# Sheet1.net
KiCad netlist of a schematic drawn in Altium Designer
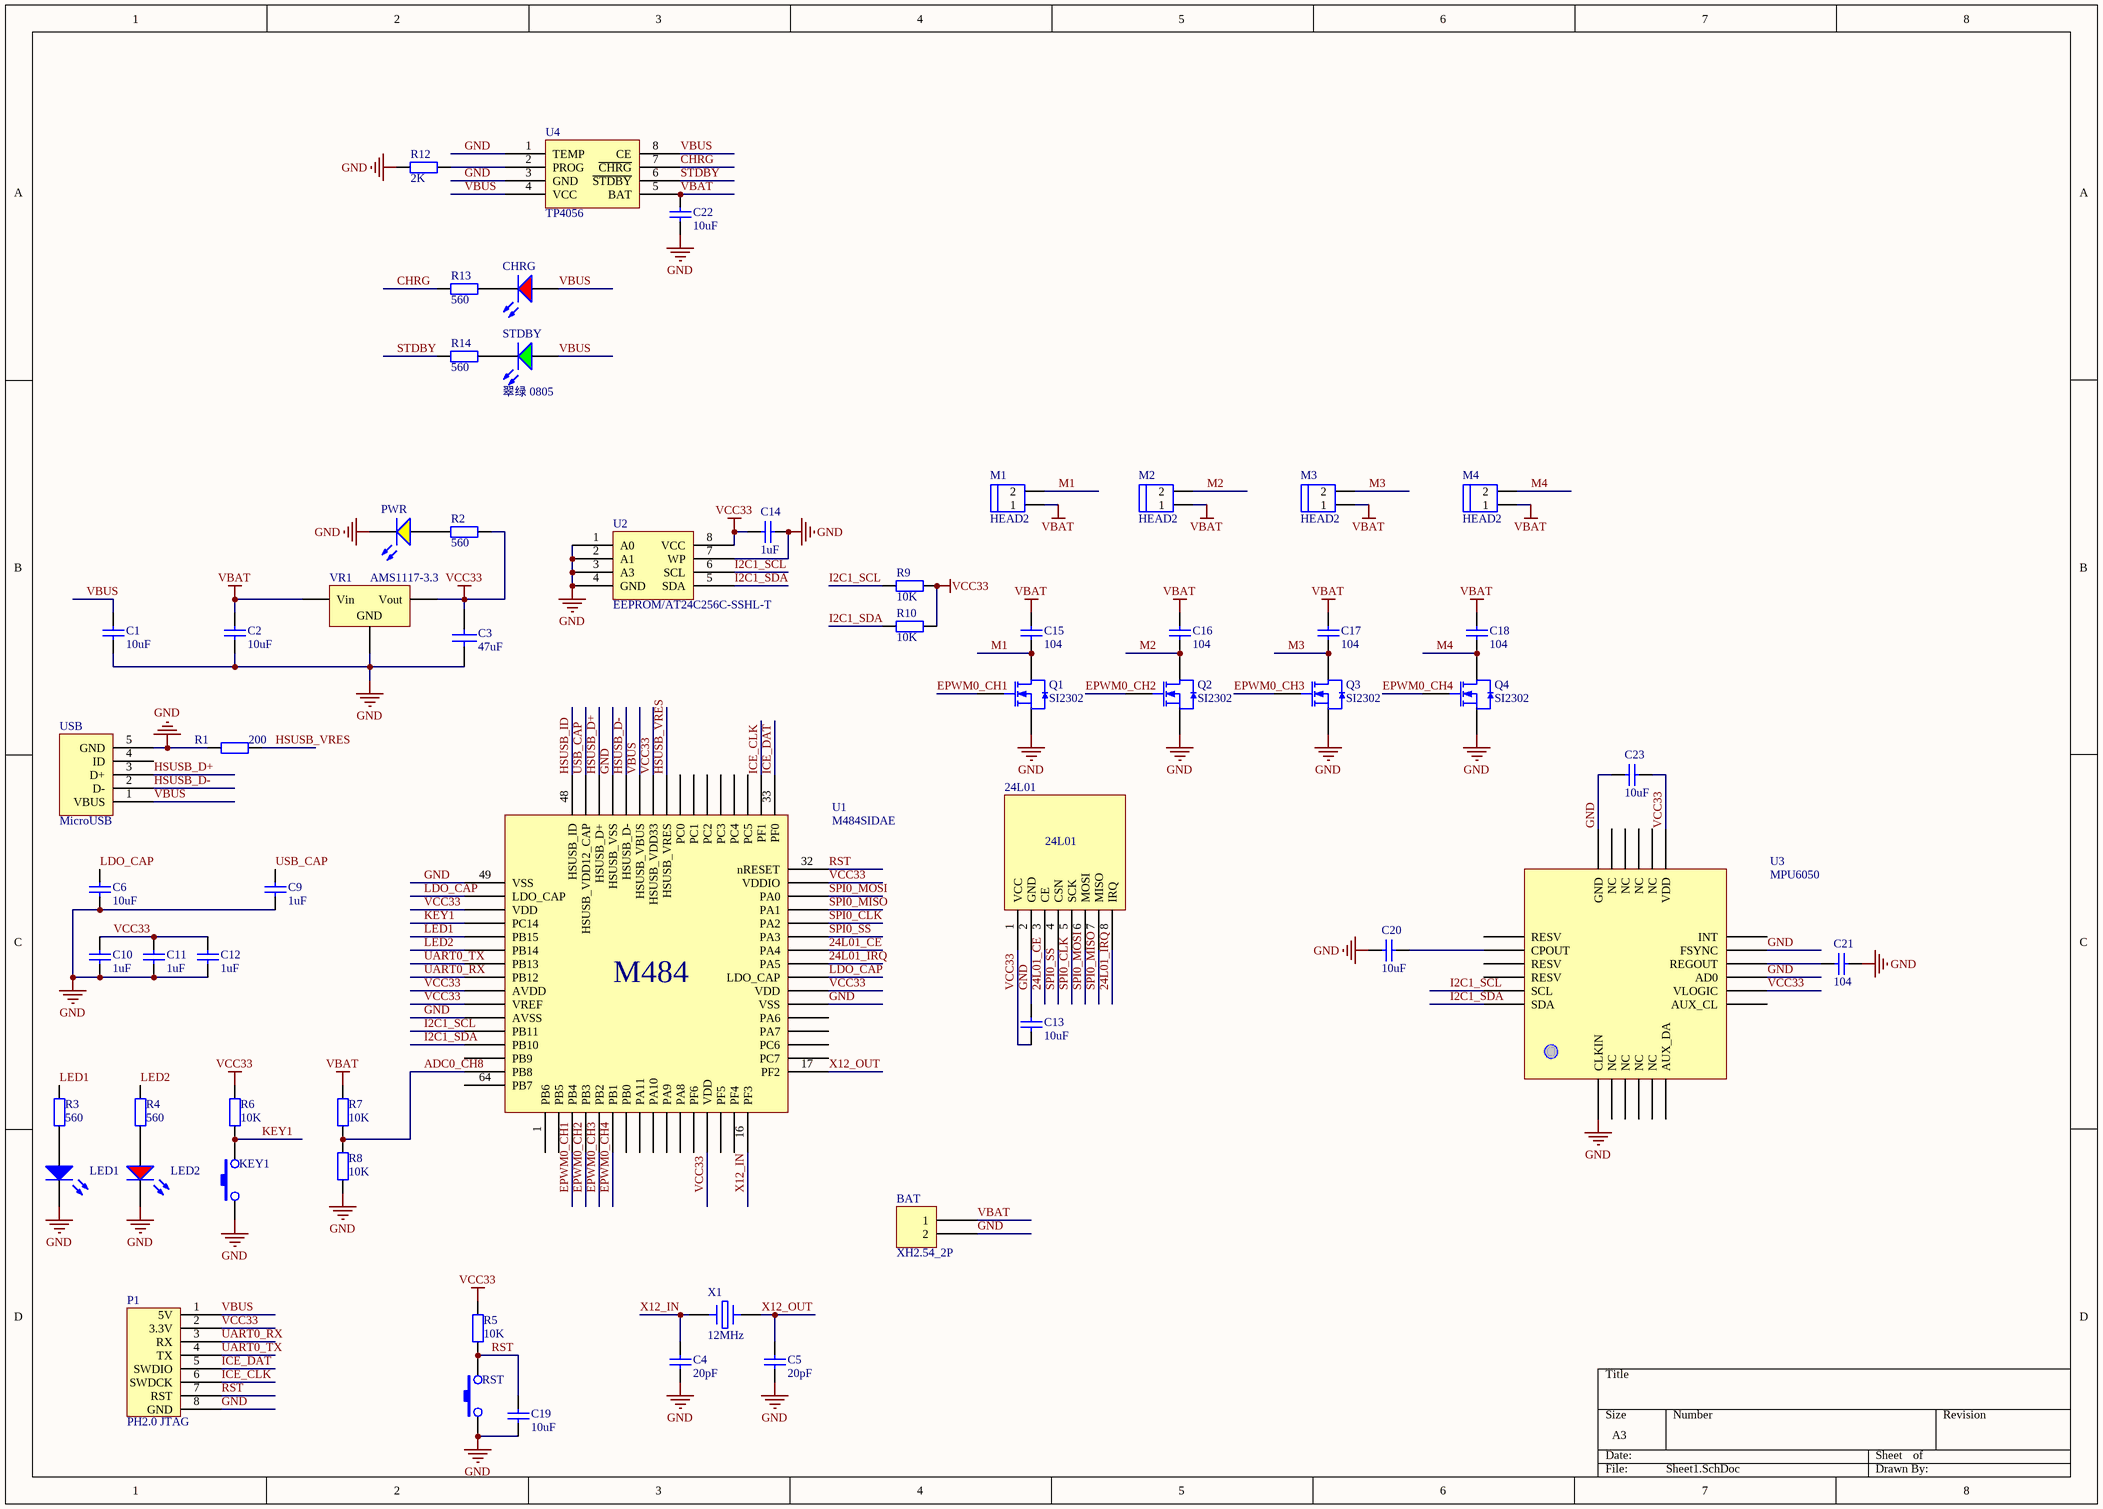
[diagram p0: Sheet1.SchDoc]

(export (version "E")
  (design (tool "Eeschema 10.0.6"))
  (components
    (comp (ref "24L01")
      (value "~")
      (footprint "NRF24L01")
      (libsource (lib "Integrated_Library2") (part "NRF24L01"))
    )
    (comp (ref "BAT")
      (value "XH2.54_2P")
      (footprint "XH_2P")
      (libsource (lib "Integrated_Library2") (part "XH2.54_2P"))
    )
    (comp (ref "C1")
      (value "10uF")
      (footprint "LC-0805_C")
      (description "贴片电容")
      (libsource (lib "JLC") (part "0805 1.5nF (152) 10% 50V"))
    )
    (comp (ref "C2")
      (value "10uF")
      (footprint "LC-0805_C")
      (description "贴片电容")
      (libsource (lib "JLC") (part "0805 1.5nF (152) 10% 50V"))
    )
    (comp (ref "C3")
      (value "47uF")
      (footprint "1206")
      (libsource (lib "Integrated_Library2") (part "Capacitor"))
    )
    (comp (ref "C4")
      (value "20pF")
      (footprint "LC-0603_C")
      (description "贴片电容")
      (libsource (lib "JLC") (part "0603 6pF (6R0) 0.25pF 50V"))
    )
    (comp (ref "C5")
      (value "20pF")
      (footprint "LC-0603_C")
      (description "贴片电容")
      (libsource (lib "JLC") (part "0603 6pF (6R0) 0.25pF 50V"))
    )
    (comp (ref "C6")
      (value "10uF")
      (footprint "LC-0805_C")
      (description "贴片电容")
      (libsource (lib "JLC") (part "0805 1.5nF (152) 10% 50V"))
    )
    (comp (ref "C9")
      (value "1uF")
      (footprint "LC-0805_C")
      (description "贴片电容")
      (libsource (lib "JLC") (part "0805 1.5nF (152) 10% 50V"))
    )
    (comp (ref "C10")
      (value "1uF")
      (footprint "LC-0805_C")
      (description "贴片电容")
      (libsource (lib "JLC") (part "0805 1.5nF (152) 10% 50V"))
    )
    (comp (ref "C11")
      (value "1uF")
      (footprint "LC-0805_C")
      (description "贴片电容")
      (libsource (lib "JLC") (part "0805 1.5nF (152) 10% 50V"))
    )
    (comp (ref "C12")
      (value "1uF")
      (footprint "LC-0805_C")
      (description "贴片电容")
      (libsource (lib "JLC") (part "0805 1.5nF (152) 10% 50V"))
    )
    (comp (ref "C13")
      (value "10uF")
      (footprint "LC-0805_C")
      (description "贴片电容")
      (libsource (lib "JLC") (part "0805 1.5nF (152) 10% 50V"))
    )
    (comp (ref "C14")
      (value "1uF")
      (footprint "LC-0805_C")
      (description "贴片电容")
      (libsource (lib "JLC") (part "0805 1.5nF (152) 10% 50V"))
    )
    (comp (ref "C15")
      (value "104")
      (footprint "LC-0603_C")
      (description "贴片电容")
      (libsource (lib "JLC") (part "0603 6pF (6R0) 0.25pF 50V"))
    )
    (comp (ref "C16")
      (value "104")
      (footprint "LC-0603_C")
      (description "贴片电容")
      (libsource (lib "JLC") (part "0603 6pF (6R0) 0.25pF 50V"))
    )
    (comp (ref "C17")
      (value "104")
      (footprint "LC-0603_C")
      (description "贴片电容")
      (libsource (lib "JLC") (part "0603 6pF (6R0) 0.25pF 50V"))
    )
    (comp (ref "C18")
      (value "104")
      (footprint "LC-0603_C")
      (description "贴片电容")
      (libsource (lib "JLC") (part "0603 6pF (6R0) 0.25pF 50V"))
    )
    (comp (ref "C19")
      (value "10uF")
      (footprint "LC-0805_C")
      (description "贴片电容")
      (libsource (lib "JLC") (part "0805 1.5nF (152) 10% 50V"))
    )
    (comp (ref "C20")
      (value "10uF")
      (footprint "LC-0805_C")
      (description "贴片电容")
      (libsource (lib "JLC") (part "0805 1.5nF (152) 10% 50V"))
    )
    (comp (ref "C21")
      (value "104")
      (footprint "LC-0603_C")
      (description "贴片电容")
      (libsource (lib "JLC") (part "0603 6pF (6R0) 0.25pF 50V"))
    )
    (comp (ref "C22")
      (value "10uF")
      (footprint "LC-0805_C")
      (description "贴片电容")
      (libsource (lib "JLC") (part "0805 1.5nF (152) 10% 50V"))
    )
    (comp (ref "C23")
      (value "10uF")
      (footprint "LC-0805_C")
      (description "贴片电容")
      (libsource (lib "JLC") (part "0805 1.5nF (152) 10% 50V"))
    )
    (comp (ref "CHRG")
      (value "~")
      (footprint "LC-0805_LED_S1")
      (description "发光二极管")
      (libsource (lib "JLC") (part "0805 红灯"))
    )
    (comp (ref "KEY1") (value "~") (footprint "KEY2") (libsource (lib "Integrated_Library2") (part "KEY")))
    (comp (ref "LED1")
      (value "~")
      (footprint "LC-0805_LED_S1")
      (description "发光二极管")
      (libsource (lib "JLC") (part "0805 蓝灯"))
    )
    (comp (ref "LED2")
      (value "~")
      (footprint "LC-0805_LED_S1")
      (description "发光二极管")
      (libsource (lib "JLC") (part "0805 红灯"))
    )
    (comp (ref "M1") (value "HEAD2") (footprint "HEADER2-1.25MM") (libsource (lib "MiniFly ") (part "HEAD2")))
    (comp (ref "M2") (value "HEAD2") (footprint "HEADER2-1.25MM") (libsource (lib "MiniFly ") (part "HEAD2")))
    (comp (ref "M3") (value "HEAD2") (footprint "HEADER2-1.25MM") (libsource (lib "MiniFly ") (part "HEAD2")))
    (comp (ref "M4") (value "HEAD2") (footprint "HEADER2-1.25MM") (libsource (lib "MiniFly ") (part "HEAD2")))
    (comp (ref "P1")
      (value "PH2.0 JTAG")
      (footprint "PH2.0 8P")
      (libsource (lib "Integrated_Library2") (part "PH2.0 JTAG"))
    )
    (comp (ref "PWR")
      (value "~")
      (footprint "LC-0805_LED_S1")
      (description "发光二极管")
      (libsource (lib "JLC") (part "0805 黄灯"))
    )
    (comp (ref "Q1")
      (value "SI2302")
      (footprint "LC-SOT-23(SOT-23-3)")
      (description "MOS(场效应管)")
      (libsource (lib "JLC") (part "2N7002 7002"))
    )
    (comp (ref "Q2")
      (value "SI2302")
      (footprint "LC-SOT-23(SOT-23-3)")
      (description "MOS(场效应管)")
      (libsource (lib "JLC") (part "2N7002 7002"))
    )
    (comp (ref "Q3")
      (value "SI2302")
      (footprint "LC-SOT-23(SOT-23-3)")
      (description "MOS(场效应管)")
      (libsource (lib "JLC") (part "2N7002 7002"))
    )
    (comp (ref "Q4")
      (value "SI2302")
      (footprint "LC-SOT-23(SOT-23-3)")
      (description "MOS(场效应管)")
      (libsource (lib "JLC") (part "2N7002 7002"))
    )
    (comp (ref "R1")
      (value "200")
      (footprint "LC-0603_R")
      (description "贴片电阻")
      (libsource (lib "") (part "0603 2.4KΩ (2401) 1%_1"))
    )
    (comp (ref "R2")
      (value "560")
      (footprint "LC-0603_R")
      (description "贴片电阻")
      (libsource (lib "") (part "0603 2.4KΩ (2401) 1%_1"))
    )
    (comp (ref "R3")
      (value "560")
      (footprint "LC-0603_R")
      (description "贴片电阻")
      (libsource (lib "JLC") (part "0603 2.4KΩ (2401) 1%"))
    )
    (comp (ref "R4")
      (value "560")
      (footprint "LC-0603_R")
      (description "贴片电阻")
      (libsource (lib "JLC") (part "0603 2.4KΩ (2401) 1%"))
    )
    (comp (ref "R5")
      (value "10K")
      (footprint "LC-0603_R")
      (description "贴片电阻")
      (libsource (lib "JLC") (part "0603 2.4KΩ (2401) 1%"))
    )
    (comp (ref "R6")
      (value "10K")
      (footprint "LC-0603_R")
      (description "贴片电阻")
      (libsource (lib "JLC") (part "0603 2.4KΩ (2401) 1%"))
    )
    (comp (ref "R7")
      (value "10K")
      (footprint "LC-0603_R")
      (description "贴片电阻")
      (libsource (lib "JLC") (part "0603 2.4KΩ (2401) 1%"))
    )
    (comp (ref "R8")
      (value "10K")
      (footprint "LC-0603_R")
      (description "贴片电阻")
      (libsource (lib "JLC") (part "0603 2.4KΩ (2401) 1%"))
    )
    (comp (ref "R9")
      (value "10K")
      (footprint "LC-0603_R")
      (description "贴片电阻")
      (libsource (lib "") (part "0603 2.4KΩ (2401) 1%_1"))
    )
    (comp (ref "R10")
      (value "10K")
      (footprint "LC-0603_R")
      (description "贴片电阻")
      (libsource (lib "") (part "0603 2.4KΩ (2401) 1%_1"))
    )
    (comp (ref "R12")
      (value "2K")
      (footprint "LC-0603_R")
      (description "贴片电阻")
      (libsource (lib "") (part "0603 2.4KΩ (2401) 1%_1"))
    )
    (comp (ref "R13")
      (value "560")
      (footprint "LC-0603_R")
      (description "贴片电阻")
      (libsource (lib "") (part "0603 2.4KΩ (2401) 1%_1"))
    )
    (comp (ref "R14")
      (value "560")
      (footprint "LC-0603_R")
      (description "贴片电阻")
      (libsource (lib "") (part "0603 2.4KΩ (2401) 1%_1"))
    )
    (comp (ref "RST") (value "~") (footprint "KEY2") (libsource (lib "Integrated_Library2") (part "KEY")))
    (comp (ref "STDBY")
      (value "翠绿 0805")
      (footprint "LC-0805_LED_S1")
      (description "发光二极管")
      (libsource (lib "JLC") (part "0805 翠绿"))
    )
    (comp (ref "U1")
      (value "M484SIDAE")
      (footprint "LQFP64L")
      (libsource (lib "Integrated_Library2") (part "M484SIDAE"))
    )
    (comp (ref "U2")
      (value "EEPROM/AT24C256C-SSHL-T")
      (footprint "LC-SOIC-8_150mil")
      (description "EEPROM")
      (libsource (lib "JLC") (part "EEPROM/AT24C256C-SSHL-T"))
    )
    (comp (ref "U3")
      (value "MPU6050")
      (footprint "QFN-24_4x4x05P")
      (libsource (lib "Integrated_Library2") (part "MPU6050"))
    )
    (comp (ref "U4")
      (value "TP4056")
      (footprint "LC-SOP-8_EP_150mil")
      (description "电池电源管理")
      (libsource (lib "JLC") (part "TP4056"))
    )
    (comp (ref "USB")
      (value "MicroUSB")
      (footprint "MICROUSB1")
      (libsource (lib "Integrated_Library2") (part "MicroUSB"))
    )
    (comp (ref "VR1")
      (value "AMS1117-3.3")
      (footprint "LC-SOT-223")
      (description "低压差线性稳压(LDO)")
      (libsource (lib "JLC") (part "SOT-223 AMS1117-3.3"))
    )
    (comp (ref "X1")
      (value "12MHz")
      (footprint "XTAL1")
      (libsource (lib "Integrated_Library2") (part "XTAL"))
    )
  )
  (nets
    (net (code "1") (name "/24L01_CE") (class "Default")
      (node (ref "24L01") (pin "3") (pinfunction "CE_3") (pintype "passive"))
      (node (ref "U1") (pin "26") (pinfunction "PA4_26") (pintype "passive"))
    )
    (net (code "2") (name "/24L01_IRQ") (class "Default")
      (node (ref "24L01") (pin "8") (pinfunction "IRQ_8") (pintype "passive"))
      (node (ref "U1") (pin "25") (pinfunction "PA5_25") (pintype "passive"))
    )
    (net (code "3") (name "/ADC0_CH8") (class "Default")
      (node (ref "R7") (pin "1") (pinfunction "1_1") (pintype "passive"))
      (node (ref "R8") (pin "2") (pinfunction "2_2") (pintype "passive"))
      (node (ref "U1") (pin "63") (pinfunction "PB8_63") (pintype "passive"))
    )
    (net (code "4") (name "/CHRG") (class "Default")
      (node (ref "R13") (pin "1") (pinfunction "1_1") (pintype "passive"))
      (node (ref "U4") (pin "7") (pinfunction "~{CHRG}_7") (pintype "passive"))
    )
    (net (code "5") (name "/EPWM0_CH1") (class "Default")
      (node (ref "Q1") (pin "1") (pinfunction "G_1") (pintype "passive"))
      (node (ref "U1") (pin "3") (pinfunction "PB4_3") (pintype "passive"))
    )
    (net (code "6") (name "/EPWM0_CH2") (class "Default")
      (node (ref "Q2") (pin "1") (pinfunction "G_1") (pintype "passive"))
      (node (ref "U1") (pin "4") (pinfunction "PB3_4") (pintype "passive"))
    )
    (net (code "7") (name "/EPWM0_CH3") (class "Default")
      (node (ref "Q3") (pin "1") (pinfunction "G_1") (pintype "passive"))
      (node (ref "U1") (pin "5") (pinfunction "PB2_5") (pintype "passive"))
    )
    (net (code "8") (name "/EPWM0_CH4") (class "Default")
      (node (ref "Q4") (pin "1") (pinfunction "G_1") (pintype "passive"))
      (node (ref "U1") (pin "6") (pinfunction "PB1_6") (pintype "passive"))
    )
    (net (code "9") (name "/HSUSB_D+") (class "Default")
      (node (ref "U1") (pin "46") (pinfunction "HSUSB_D+_46") (pintype "passive"))
      (node (ref "USB") (pin "3") (pinfunction "D+_3") (pintype "passive"))
    )
    (net (code "10") (name "/HSUSB_D-") (class "Default")
      (node (ref "U1") (pin "44") (pinfunction "HSUSB_D-_44") (pintype "passive"))
      (node (ref "USB") (pin "2") (pinfunction "D-_2") (pintype "passive"))
    )
    (net (code "11") (name "/HSUSB_ID") (class "Default")
      (node (ref "U1") (pin "48") (pinfunction "HSUSB_ID_48") (pintype "passive"))
    )
    (net (code "12") (name "/HSUSB_VRES") (class "Default")
      (node (ref "R1") (pin "2") (pinfunction "2_2") (pintype "passive"))
      (node (ref "U1") (pin "41") (pinfunction "HSUSB_VRES_41") (pintype "passive"))
    )
    (net (code "13") (name "/I2C1_SCL") (class "Default")
      (node (ref "R9") (pin "1") (pinfunction "1_1") (pintype "passive"))
      (node (ref "U1") (pin "60") (pinfunction "PB11_60") (pintype "passive"))
      (node (ref "U2") (pin "6") (pinfunction "SCL_6") (pintype "passive"))
      (node (ref "U3") (pin "23") (pinfunction "SCL_23") (pintype "passive"))
    )
    (net (code "14") (name "/I2C1_SDA") (class "Default")
      (node (ref "R10") (pin "1") (pinfunction "1_1") (pintype "passive"))
      (node (ref "U1") (pin "61") (pinfunction "PB10_61") (pintype "passive"))
      (node (ref "U2") (pin "5") (pinfunction "SDA_5") (pintype "passive"))
      (node (ref "U3") (pin "24") (pinfunction "SDA_24") (pintype "passive"))
    )
    (net (code "15") (name "/ICE_CLK") (class "Default")
      (node (ref "P1") (pin "6") (pinfunction "SWDCK_6") (pintype "passive"))
      (node (ref "U1") (pin "34") (pinfunction "PF1_34") (pintype "passive"))
    )
    (net (code "16") (name "/ICE_DAT") (class "Default")
      (node (ref "P1") (pin "5") (pinfunction "SWDIO_5") (pintype "passive"))
      (node (ref "U1") (pin "33") (pinfunction "PF0_33") (pintype "passive"))
    )
    (net (code "17") (name "/KEY1") (class "Default")
      (node (ref "KEY1") (pin "2") (pinfunction "2_2") (pintype "passive"))
      (node (ref "R6") (pin "1") (pinfunction "1_1") (pintype "passive"))
      (node (ref "U1") (pin "52") (pinfunction "PC14_52") (pintype "passive"))
    )
    (net (code "18") (name "/LDO_CAP") (class "Default")
      (node (ref "C6") (pin "2") (pinfunction "2_2") (pintype "passive"))
      (node (ref "U1") (pin "24") (pinfunction "LDO_CAP_24") (pintype "passive"))
      (node (ref "U1") (pin "50") (pinfunction "LDO_CAP_50") (pintype "passive"))
    )
    (net (code "19") (name "/LED1") (class "Default")
      (node (ref "R3") (pin "2") (pinfunction "2_2") (pintype "passive"))
      (node (ref "U1") (pin "53") (pinfunction "PB15_53") (pintype "passive"))
    )
    (net (code "20") (name "/LED2") (class "Default")
      (node (ref "R4") (pin "2") (pinfunction "2_2") (pintype "passive"))
      (node (ref "U1") (pin "54") (pinfunction "PB14_54") (pintype "passive"))
    )
    (net (code "21") (name "/M1") (class "Default")
      (node (ref "C15") (pin "1") (pinfunction "1_1") (pintype "passive"))
      (node (ref "M1") (pin "2") (pinfunction "2_2") (pintype "passive"))
      (node (ref "Q1") (pin "3") (pinfunction "D_3") (pintype "passive"))
    )
    (net (code "22") (name "/M2") (class "Default")
      (node (ref "C16") (pin "1") (pinfunction "1_1") (pintype "passive"))
      (node (ref "M2") (pin "2") (pinfunction "2_2") (pintype "passive"))
      (node (ref "Q2") (pin "3") (pinfunction "D_3") (pintype "passive"))
    )
    (net (code "23") (name "/M3") (class "Default")
      (node (ref "C17") (pin "1") (pinfunction "1_1") (pintype "passive"))
      (node (ref "M3") (pin "2") (pinfunction "2_2") (pintype "passive"))
      (node (ref "Q3") (pin "3") (pinfunction "D_3") (pintype "passive"))
    )
    (net (code "24") (name "/M4") (class "Default")
      (node (ref "C18") (pin "1") (pinfunction "1_1") (pintype "passive"))
      (node (ref "M4") (pin "2") (pinfunction "2_2") (pintype "passive"))
      (node (ref "Q4") (pin "3") (pinfunction "D_3") (pintype "passive"))
    )
    (net (code "25") (name "/RST") (class "Default")
      (node (ref "C19") (pin "2") (pinfunction "2_2") (pintype "passive"))
      (node (ref "P1") (pin "7") (pinfunction "RST_7") (pintype "passive"))
      (node (ref "R5") (pin "1") (pinfunction "1_1") (pintype "passive"))
      (node (ref "RST") (pin "2") (pinfunction "2_2") (pintype "passive"))
      (node (ref "U1") (pin "32") (pinfunction "nRESET_32") (pintype "passive"))
    )
    (net (code "26") (name "/SPI0_CLK") (class "Default")
      (node (ref "24L01") (pin "5") (pinfunction "SCK_5") (pintype "passive"))
      (node (ref "U1") (pin "28") (pinfunction "PA2_28") (pintype "passive"))
    )
    (net (code "27") (name "/SPI0_MISO") (class "Default")
      (node (ref "24L01") (pin "7") (pinfunction "MISO_7") (pintype "passive"))
      (node (ref "U1") (pin "29") (pinfunction "PA1_29") (pintype "passive"))
    )
    (net (code "28") (name "/SPI0_MOSI") (class "Default")
      (node (ref "24L01") (pin "6") (pinfunction "MOSI_6") (pintype "passive"))
      (node (ref "U1") (pin "30") (pinfunction "PA0_30") (pintype "passive"))
    )
    (net (code "29") (name "/SPI0_SS") (class "Default")
      (node (ref "24L01") (pin "4") (pinfunction "CSN_4") (pintype "passive"))
      (node (ref "U1") (pin "27") (pinfunction "PA3_27") (pintype "passive"))
    )
    (net (code "30") (name "/STDBY") (class "Default")
      (node (ref "R14") (pin "1") (pinfunction "1_1") (pintype "passive"))
      (node (ref "U4") (pin "6") (pinfunction "~{STDBY}_6") (pintype "passive"))
    )
    (net (code "31") (name "/UART0_RX") (class "Default")
      (node (ref "P1") (pin "3") (pinfunction "RX_3") (pintype "passive"))
      (node (ref "U1") (pin "56") (pinfunction "PB12_56") (pintype "passive"))
    )
    (net (code "32") (name "/UART0_TX") (class "Default")
      (node (ref "P1") (pin "4") (pinfunction "TX_4") (pintype "passive"))
      (node (ref "U1") (pin "55") (pinfunction "PB13_55") (pintype "passive"))
    )
    (net (code "33") (name "/USB_CAP") (class "Default")
      (node (ref "C9") (pin "2") (pinfunction "2_2") (pintype "passive"))
      (node (ref "U1") (pin "47") (pinfunction "HSUSB_VDD12_CAP_47") (pintype "passive"))
    )
    (net (code "34") (name "/VBUS") (class "Default")
      (node (ref "C1") (pin "2") (pinfunction "2_2") (pintype "passive"))
      (node (ref "CHRG") (pin "A") (pinfunction "A_A") (pintype "passive"))
      (node (ref "P1") (pin "1") (pinfunction "5V_1") (pintype "passive"))
      (node (ref "STDBY") (pin "A") (pinfunction "A_A") (pintype "passive"))
      (node (ref "U1") (pin "43") (pinfunction "HSUSB_VBUS_43") (pintype "passive"))
      (node (ref "U4") (pin "4") (pinfunction "VCC_4") (pintype "passive"))
      (node (ref "U4") (pin "8") (pinfunction "CE_8") (pintype "passive"))
      (node (ref "USB") (pin "1") (pinfunction "VBUS_1") (pintype "passive"))
    )
    (net (code "35") (name "/X12_IN") (class "Default")
      (node (ref "C4") (pin "2") (pinfunction "2_2") (pintype "passive"))
      (node (ref "U1") (pin "16") (pinfunction "PF3_16") (pintype "passive"))
      (node (ref "X1") (pin "1") (pinfunction "1_1") (pintype "passive"))
    )
    (net (code "36") (name "/X12_OUT") (class "Default")
      (node (ref "C5") (pin "2") (pinfunction "2_2") (pintype "passive"))
      (node (ref "U1") (pin "17") (pinfunction "PF2_17") (pintype "passive"))
      (node (ref "X1") (pin "2") (pinfunction "2_2") (pintype "passive"))
    )
    (net (code "37") (name "GND") (class "Default")
      (node (ref "24L01") (pin "2") (pinfunction "GND_2") (pintype "passive"))
      (node (ref "BAT") (pin "2") (pinfunction "2_2") (pintype "passive"))
      (node (ref "C1") (pin "1") (pinfunction "1_1") (pintype "passive"))
      (node (ref "C10") (pin "1") (pinfunction "1_1") (pintype "passive"))
      (node (ref "C11") (pin "1") (pinfunction "1_1") (pintype "passive"))
      (node (ref "C12") (pin "1") (pinfunction "1_1") (pintype "passive"))
      (node (ref "C13") (pin "2") (pinfunction "2_2") (pintype "passive"))
      (node (ref "C14") (pin "1") (pinfunction "1_1") (pintype "passive"))
      (node (ref "C19") (pin "1") (pinfunction "1_1") (pintype "passive"))
      (node (ref "C2") (pin "1") (pinfunction "1_1") (pintype "passive"))
      (node (ref "C20") (pin "2") (pinfunction "2_2") (pintype "passive"))
      (node (ref "C21") (pin "1") (pinfunction "1_1") (pintype "passive"))
      (node (ref "C22") (pin "1") (pinfunction "1_1") (pintype "passive"))
      (node (ref "C23") (pin "2") (pinfunction "2_2") (pintype "passive"))
      (node (ref "C3") (pin "1") (pinfunction "1_1") (pintype "passive"))
      (node (ref "C4") (pin "1") (pinfunction "1_1") (pintype "passive"))
      (node (ref "C5") (pin "1") (pinfunction "1_1") (pintype "passive"))
      (node (ref "C6") (pin "1") (pinfunction "1_1") (pintype "passive"))
      (node (ref "C9") (pin "1") (pinfunction "1_1") (pintype "passive"))
      (node (ref "KEY1") (pin "1") (pinfunction "1_1") (pintype "passive"))
      (node (ref "LED1") (pin "K") (pinfunction "K_K") (pintype "passive"))
      (node (ref "LED2") (pin "K") (pinfunction "K_K") (pintype "passive"))
      (node (ref "P1") (pin "8") (pinfunction "GND_8") (pintype "passive"))
      (node (ref "PWR") (pin "K") (pinfunction "K_K") (pintype "passive"))
      (node (ref "Q1") (pin "2") (pinfunction "S_2") (pintype "passive"))
      (node (ref "Q2") (pin "2") (pinfunction "S_2") (pintype "passive"))
      (node (ref "Q3") (pin "2") (pinfunction "S_2") (pintype "passive"))
      (node (ref "Q4") (pin "2") (pinfunction "S_2") (pintype "passive"))
      (node (ref "R1") (pin "1") (pinfunction "1_1") (pintype "passive"))
      (node (ref "R12") (pin "1") (pinfunction "1_1") (pintype "passive"))
      (node (ref "R8") (pin "1") (pinfunction "1_1") (pintype "passive"))
      (node (ref "RST") (pin "1") (pinfunction "1_1") (pintype "passive"))
      (node (ref "U1") (pin "22") (pinfunction "VSS_22") (pintype "passive"))
      (node (ref "U1") (pin "45") (pinfunction "HSUSB_VSS_45") (pintype "passive"))
      (node (ref "U1") (pin "49") (pinfunction "VSS_49") (pintype "passive"))
      (node (ref "U1") (pin "59") (pinfunction "AVSS_59") (pintype "passive"))
      (node (ref "U2") (pin "1") (pinfunction "A0_1") (pintype "passive"))
      (node (ref "U2") (pin "2") (pinfunction "A1_2") (pintype "passive"))
      (node (ref "U2") (pin "3") (pinfunction "A3_3") (pintype "passive"))
      (node (ref "U2") (pin "4") (pinfunction "GND_4") (pintype "passive"))
      (node (ref "U2") (pin "7") (pinfunction "WP_7") (pintype "passive"))
      (node (ref "U3") (pin "1") (pinfunction "CLKIN_1") (pintype "passive"))
      (node (ref "U3") (pin "11") (pinfunction "FSYNC_11") (pintype "passive"))
      (node (ref "U3") (pin "18") (pinfunction "GND_18") (pintype "passive"))
      (node (ref "U3") (pin "9") (pinfunction "AD0_9") (pintype "passive"))
      (node (ref "U4") (pin "1") (pinfunction "TEMP_1") (pintype "passive"))
      (node (ref "U4") (pin "3") (pinfunction "GND_3") (pintype "passive"))
      (node (ref "USB") (pin "5") (pinfunction "GND_5") (pintype "passive"))
      (node (ref "VR1") (pin "1") (pinfunction "GND_1") (pintype "passive"))
    )
    (net (code "38") (name "Net-(CHRG-PadK)") (class "Default")
      (node (ref "CHRG") (pin "K") (pinfunction "K_K") (pintype "passive"))
      (node (ref "R13") (pin "2") (pinfunction "2_2") (pintype "passive"))
    )
    (net (code "39") (name "Net-(LED1-PadA)") (class "Default")
      (node (ref "LED1") (pin "A") (pinfunction "A_A") (pintype "passive"))
      (node (ref "R3") (pin "1") (pinfunction "1_1") (pintype "passive"))
    )
    (net (code "40") (name "Net-(LED2-PadA)") (class "Default")
      (node (ref "LED2") (pin "A") (pinfunction "A_A") (pintype "passive"))
      (node (ref "R4") (pin "1") (pinfunction "1_1") (pintype "passive"))
    )
    (net (code "41") (name "Net-(PWR-PadA)") (class "Default")
      (node (ref "PWR") (pin "A") (pinfunction "A_A") (pintype "passive"))
      (node (ref "R2") (pin "1") (pinfunction "1_1") (pintype "passive"))
    )
    (net (code "42") (name "Net-(R14-Pad2)") (class "Default")
      (node (ref "R14") (pin "2") (pinfunction "2_2") (pintype "passive"))
      (node (ref "STDBY") (pin "K") (pinfunction "K_K") (pintype "passive"))
    )
    (net (code "43") (name "Net-(U3-CPOUT)") (class "Default")
      (node (ref "C20") (pin "1") (pinfunction "1_1") (pintype "passive"))
      (node (ref "U3") (pin "20") (pinfunction "CPOUT_20") (pintype "passive"))
    )
    (net (code "44") (name "Net-(U3-REGOUT)") (class "Default")
      (node (ref "C21") (pin "2") (pinfunction "2_2") (pintype "passive"))
      (node (ref "U3") (pin "10") (pinfunction "REGOUT_10") (pintype "passive"))
    )
    (net (code "45") (name "Net-(U4-PROG)") (class "Default")
      (node (ref "R12") (pin "2") (pinfunction "2_2") (pintype "passive"))
      (node (ref "U4") (pin "2") (pinfunction "PROG_2") (pintype "passive"))
    )
    (net (code "46") (name "VBAT") (class "Default")
      (node (ref "BAT") (pin "1") (pinfunction "1_1") (pintype "passive"))
      (node (ref "C15") (pin "2") (pinfunction "2_2") (pintype "passive"))
      (node (ref "C16") (pin "2") (pinfunction "2_2") (pintype "passive"))
      (node (ref "C17") (pin "2") (pinfunction "2_2") (pintype "passive"))
      (node (ref "C18") (pin "2") (pinfunction "2_2") (pintype "passive"))
      (node (ref "C2") (pin "2") (pinfunction "2_2") (pintype "passive"))
      (node (ref "C22") (pin "2") (pinfunction "2_2") (pintype "passive"))
      (node (ref "M1") (pin "1") (pinfunction "1_1") (pintype "passive"))
      (node (ref "M2") (pin "1") (pinfunction "1_1") (pintype "passive"))
      (node (ref "M3") (pin "1") (pinfunction "1_1") (pintype "passive"))
      (node (ref "M4") (pin "1") (pinfunction "1_1") (pintype "passive"))
      (node (ref "R7") (pin "2") (pinfunction "2_2") (pintype "passive"))
      (node (ref "U4") (pin "5") (pinfunction "BAT_5") (pintype "passive"))
      (node (ref "VR1") (pin "3") (pinfunction "Vin_3") (pintype "passive"))
    )
    (net (code "47") (name "VCC33") (class "Default")
      (node (ref "24L01") (pin "1") (pinfunction "VCC_1") (pintype "passive"))
      (node (ref "C10") (pin "2") (pinfunction "2_2") (pintype "passive"))
      (node (ref "C11") (pin "2") (pinfunction "2_2") (pintype "passive"))
      (node (ref "C12") (pin "2") (pinfunction "2_2") (pintype "passive"))
      (node (ref "C13") (pin "1") (pinfunction "1_1") (pintype "passive"))
      (node (ref "C14") (pin "2") (pinfunction "2_2") (pintype "passive"))
      (node (ref "C23") (pin "1") (pinfunction "1_1") (pintype "passive"))
      (node (ref "C3") (pin "2") (pinfunction "2_2") (pintype "passive"))
      (node (ref "P1") (pin "2") (pinfunction "3.3V_2") (pintype "passive"))
      (node (ref "R10") (pin "2") (pinfunction "2_2") (pintype "passive"))
      (node (ref "R2") (pin "2") (pinfunction "2_2") (pintype "passive"))
      (node (ref "R5") (pin "2") (pinfunction "2_2") (pintype "passive"))
      (node (ref "R6") (pin "2") (pinfunction "2_2") (pintype "passive"))
      (node (ref "R9") (pin "2") (pinfunction "2_2") (pintype "passive"))
      (node (ref "U1") (pin "13") (pinfunction "VDD_13") (pintype "passive"))
      (node (ref "U1") (pin "23") (pinfunction "VDD_23") (pintype "passive"))
      (node (ref "U1") (pin "31") (pinfunction "VDDIO_31") (pintype "passive"))
      (node (ref "U1") (pin "42") (pinfunction "HSUSB_VDD33_42") (pintype "passive"))
      (node (ref "U1") (pin "51") (pinfunction "VDD_51") (pintype "passive"))
      (node (ref "U1") (pin "57") (pinfunction "AVDD_57") (pintype "passive"))
      (node (ref "U1") (pin "58") (pinfunction "VREF_58") (pintype "passive"))
      (node (ref "U2") (pin "8") (pinfunction "VCC_8") (pintype "passive"))
      (node (ref "U3") (pin "13") (pinfunction "VDD_13") (pintype "passive"))
      (node (ref "U3") (pin "8") (pinfunction "VLOGIC_8") (pintype "passive"))
      (node (ref "VR1") (pin "2") (pinfunction "Vout_2") (pintype "passive"))
    )
    (net (code "48") (name "unconnected-(U1-PA6-Pad21)") (class "Default")
      (node (ref "U1") (pin "21") (pinfunction "PA6_21") (pintype "passive"))
    )
    (net (code "49") (name "unconnected-(U1-PA7-Pad20)") (class "Default")
      (node (ref "U1") (pin "20") (pinfunction "PA7_20") (pintype "passive"))
    )
    (net (code "50") (name "unconnected-(U1-PA8-Pad11)") (class "Default")
      (node (ref "U1") (pin "11") (pinfunction "PA8_11") (pintype "passive"))
    )
    (net (code "51") (name "unconnected-(U1-PA9-Pad10)") (class "Default")
      (node (ref "U1") (pin "10") (pinfunction "PA9_10") (pintype "passive"))
    )
    (net (code "52") (name "unconnected-(U1-PA10-Pad9)") (class "Default")
      (node (ref "U1") (pin "9") (pinfunction "PA10_9") (pintype "passive"))
    )
    (net (code "53") (name "unconnected-(U1-PA11-Pad8)") (class "Default")
      (node (ref "U1") (pin "8") (pinfunction "PA11_8") (pintype "passive"))
    )
    (net (code "54") (name "unconnected-(U1-PB0-Pad7)") (class "Default")
      (node (ref "U1") (pin "7") (pinfunction "PB0_7") (pintype "passive"))
    )
    (net (code "55") (name "unconnected-(U1-PB5-Pad2)") (class "Default")
      (node (ref "U1") (pin "2") (pinfunction "PB5_2") (pintype "passive"))
    )
    (net (code "56") (name "unconnected-(U1-PB6-Pad1)") (class "Default")
      (node (ref "U1") (pin "1") (pinfunction "PB6_1") (pintype "passive"))
    )
    (net (code "57") (name "unconnected-(U1-PB7-Pad64)") (class "Default")
      (node (ref "U1") (pin "64") (pinfunction "PB7_64") (pintype "passive"))
    )
    (net (code "58") (name "unconnected-(U1-PB9-Pad62)") (class "Default")
      (node (ref "U1") (pin "62") (pinfunction "PB9_62") (pintype "passive"))
    )
    (net (code "59") (name "unconnected-(U1-PC0-Pad40)") (class "Default")
      (node (ref "U1") (pin "40") (pinfunction "PC0_40") (pintype "passive"))
    )
    (net (code "60") (name "unconnected-(U1-PC1-Pad39)") (class "Default")
      (node (ref "U1") (pin "39") (pinfunction "PC1_39") (pintype "passive"))
    )
    (net (code "61") (name "unconnected-(U1-PC2-Pad38)") (class "Default")
      (node (ref "U1") (pin "38") (pinfunction "PC2_38") (pintype "passive"))
    )
    (net (code "62") (name "unconnected-(U1-PC3-Pad37)") (class "Default")
      (node (ref "U1") (pin "37") (pinfunction "PC3_37") (pintype "passive"))
    )
    (net (code "63") (name "unconnected-(U1-PC4-Pad36)") (class "Default")
      (node (ref "U1") (pin "36") (pinfunction "PC4_36") (pintype "passive"))
    )
    (net (code "64") (name "unconnected-(U1-PC5-Pad35)") (class "Default")
      (node (ref "U1") (pin "35") (pinfunction "PC5_35") (pintype "passive"))
    )
    (net (code "65") (name "unconnected-(U1-PC6-Pad19)") (class "Default")
      (node (ref "U1") (pin "19") (pinfunction "PC6_19") (pintype "passive"))
    )
    (net (code "66") (name "unconnected-(U1-PC7-Pad18)") (class "Default")
      (node (ref "U1") (pin "18") (pinfunction "PC7_18") (pintype "passive"))
    )
    (net (code "67") (name "unconnected-(U1-PF4-Pad15)") (class "Default")
      (node (ref "U1") (pin "15") (pinfunction "PF4_15") (pintype "passive"))
    )
    (net (code "68") (name "unconnected-(U1-PF5-Pad14)") (class "Default")
      (node (ref "U1") (pin "14") (pinfunction "PF5_14") (pintype "passive"))
    )
    (net (code "69") (name "unconnected-(U1-PF6-Pad12)") (class "Default")
      (node (ref "U1") (pin "12") (pinfunction "PF6_12") (pintype "passive"))
    )
    (net (code "70") (name "unconnected-(U3-AUX_CL-Pad7)") (class "Default")
      (node (ref "U3") (pin "7") (pinfunction "AUX_CL_7") (pintype "passive"))
    )
    (net (code "71") (name "unconnected-(U3-AUX_DA-Pad6)") (class "Default")
      (node (ref "U3") (pin "6") (pinfunction "AUX_DA_6") (pintype "passive"))
    )
    (net (code "72") (name "unconnected-(U3-INT-Pad12)") (class "Default")
      (node (ref "U3") (pin "12") (pinfunction "INT_12") (pintype "passive"))
    )
    (net (code "73") (name "unconnected-(U3-NC-Pad2)") (class "Default")
      (node (ref "U3") (pin "2") (pinfunction "NC_2") (pintype "passive"))
    )
    (net (code "74") (name "unconnected-(U3-NC-Pad3)") (class "Default")
      (node (ref "U3") (pin "3") (pinfunction "NC_3") (pintype "passive"))
    )
    (net (code "75") (name "unconnected-(U3-NC-Pad4)") (class "Default")
      (node (ref "U3") (pin "4") (pinfunction "NC_4") (pintype "passive"))
    )
    (net (code "76") (name "unconnected-(U3-NC-Pad5)") (class "Default")
      (node (ref "U3") (pin "5") (pinfunction "NC_5") (pintype "passive"))
    )
    (net (code "77") (name "unconnected-(U3-NC-Pad14)") (class "Default")
      (node (ref "U3") (pin "14") (pinfunction "NC_14") (pintype "passive"))
    )
    (net (code "78") (name "unconnected-(U3-NC-Pad15)") (class "Default")
      (node (ref "U3") (pin "15") (pinfunction "NC_15") (pintype "passive"))
    )
    (net (code "79") (name "unconnected-(U3-NC-Pad16)") (class "Default")
      (node (ref "U3") (pin "16") (pinfunction "NC_16") (pintype "passive"))
    )
    (net (code "80") (name "unconnected-(U3-NC-Pad17)") (class "Default")
      (node (ref "U3") (pin "17") (pinfunction "NC_17") (pintype "passive"))
    )
    (net (code "81") (name "unconnected-(U3-RESV-Pad19)") (class "Default")
      (node (ref "U3") (pin "19") (pinfunction "RESV_19") (pintype "passive"))
    )
    (net (code "82") (name "unconnected-(U3-RESV-Pad21)") (class "Default")
      (node (ref "U3") (pin "21") (pinfunction "RESV_21") (pintype "passive"))
    )
    (net (code "83") (name "unconnected-(U3-RESV-Pad22)") (class "Default")
      (node (ref "U3") (pin "22") (pinfunction "RESV_22") (pintype "passive"))
    )
    (net (code "84") (name "unconnected-(USB-ID-Pad4)") (class "Default")
      (node (ref "USB") (pin "4") (pinfunction "ID_4") (pintype "passive"))
    )
  )
)
